# Main_sheet.net
KiCad netlist of a schematic drawn in Altium Designer
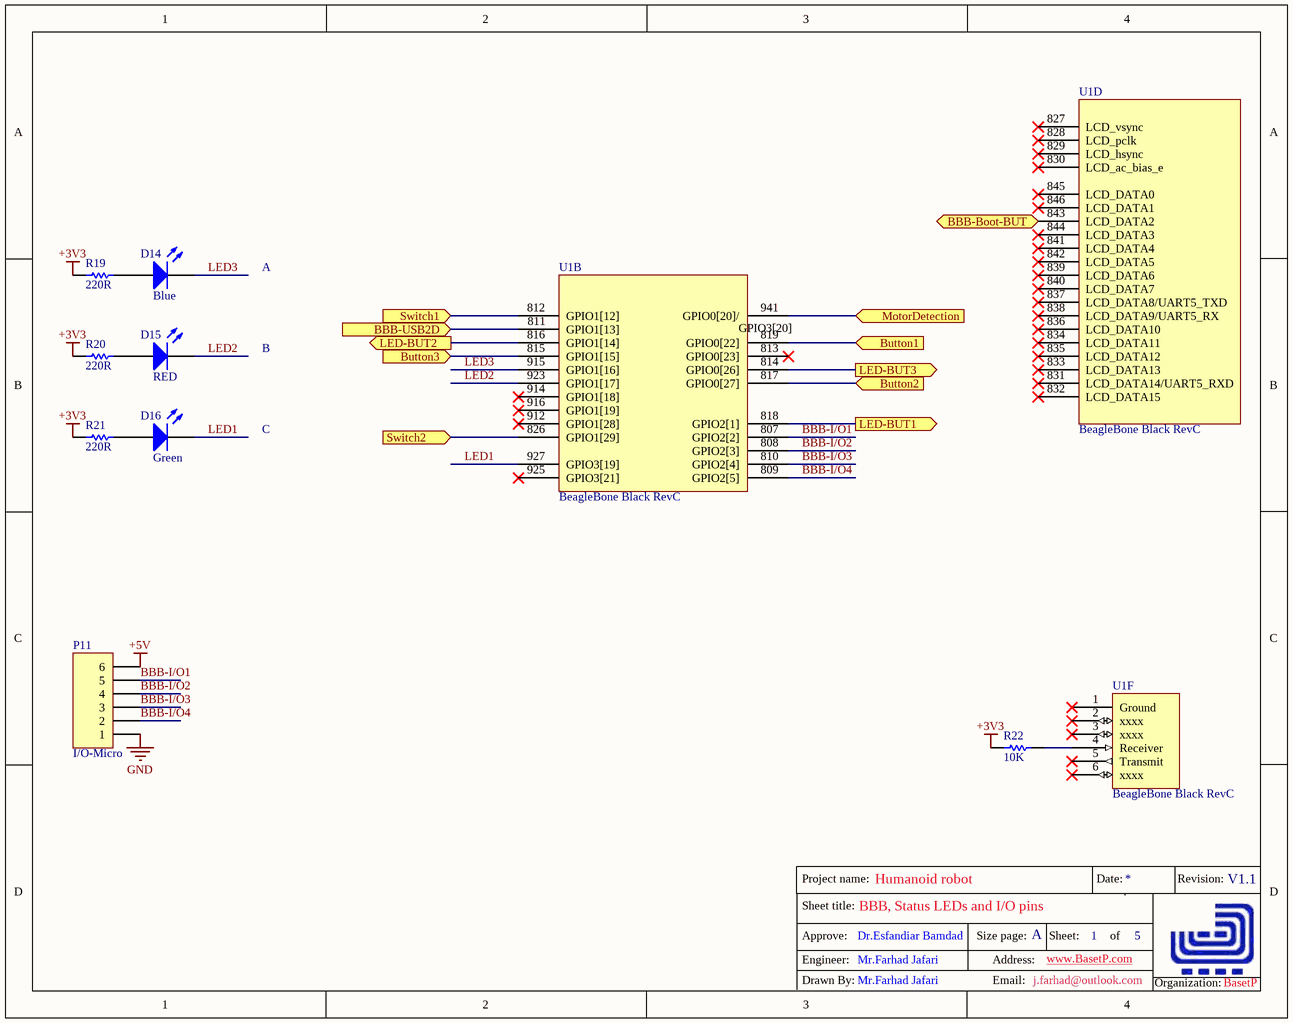
[diagram p0: Main sheet.SchDoc]

(export (version "E")
  (design (tool "Eeschema 10.0.6"))
  (components
    (comp (ref "D14")
      (value "Blue")
      (footprint "led Blue-0805")
      (description "High Performance Chip LED, Amber")
      (fields (field (name "PUBLISHER") "Altium Limited"))
      (libsource (lib "Farhad_Library") (part "LED-BLUE"))
    )
    (comp (ref "D15")
      (value "RED")
      (footprint "LED Red-0805")
      (description "High Performance Chip LED, Amber")
      (fields (field (name "PUBLISHER") "Altium Limited"))
      (libsource (lib "Farhad_Library") (part "LED-RED"))
    )
    (comp (ref "D16")
      (value "Green")
      (footprint "LED Green-0805")
      (description "High Performance Chip LED, Amber")
      (fields (field (name "PUBLISHER") "Altium Limited"))
      (libsource (lib "Farhad_Library") (part "LED-GREEN"))
    )
    (comp (ref "P11")
      (value "I/O-Micro")
      (footprint "HDR1X6")
      (description "Header, 6-Pin")
      (fields (field (name "PUBLISHER") "Altium Limited"))
      (libsource (lib "Farhad_Library") (part "Header 6"))
    )
    (comp (ref "R19")
      (value "220R")
      (footprint "6-0805")
      (fields (field (name "PUBLISHER") "Altium Limited"))
      (libsource (lib "Panasonic Resistor") (part "ERJ6RS"))
    )
    (comp (ref "R20")
      (value "220R")
      (footprint "6-0805")
      (fields (field (name "PUBLISHER") "Altium Limited"))
      (libsource (lib "Panasonic Resistor") (part "ERJ6RS"))
    )
    (comp (ref "R21")
      (value "220R")
      (footprint "6-0805")
      (fields (field (name "PUBLISHER") "Altium Limited"))
      (libsource (lib "Panasonic Resistor") (part "ERJ6RS"))
    )
    (comp (ref "R22")
      (value "10K")
      (footprint "6-0805")
      (fields (field (name "PUBLISHER") "Altium Limited"))
      (libsource (lib "Panasonic Resistor") (part "ERJ6RS"))
    )
    (comp (ref "U1")
      (value "BeagleBone Black RevC")
      (footprint "BBB-C")
      (libsource (lib "Farhad_Library") (part "BeagleBoneBlackRevC"))
    )
  )
  (nets
    (net (code "1") (name "+3V3") (class "Default")
      (node (ref "R19") (pin "1") (pinfunction "1_1") (pintype "passive"))
      (node (ref "R20") (pin "1") (pinfunction "1_1") (pintype "passive"))
      (node (ref "R21") (pin "1") (pinfunction "1_1") (pintype "passive"))
      (node (ref "R22") (pin "1") (pinfunction "1_1") (pintype "passive"))
    )
    (net (code "2") (name "+5V") (class "Default")
      (node (ref "P11") (pin "6") (pinfunction "6_6") (pintype "passive"))
    )
    (net (code "3") (name "/BBB-Boot-BUT") (class "Default")
      (node (ref "U1") (pin "843") (pinfunction "LCD_DATA2_843") (pintype "passive"))
    )
    (net (code "4") (name "/BBB-I{slash}O1") (class "Default")
      (node (ref "P11") (pin "5") (pinfunction "5_5") (pintype "passive"))
      (node (ref "U1") (pin "807") (pinfunction "GPIO2[2]_807") (pintype "passive"))
    )
    (net (code "5") (name "/BBB-I{slash}O2") (class "Default")
      (node (ref "P11") (pin "4") (pinfunction "4_4") (pintype "passive"))
      (node (ref "U1") (pin "808") (pinfunction "GPIO2[3]_808") (pintype "passive"))
    )
    (net (code "6") (name "/BBB-I{slash}O3") (class "Default")
      (node (ref "P11") (pin "3") (pinfunction "3_3") (pintype "passive"))
      (node (ref "U1") (pin "810") (pinfunction "GPIO2[4]_810") (pintype "passive"))
    )
    (net (code "7") (name "/BBB-I{slash}O4") (class "Default")
      (node (ref "P11") (pin "2") (pinfunction "2_2") (pintype "passive"))
      (node (ref "U1") (pin "809") (pinfunction "GPIO2[5]_809") (pintype "passive"))
    )
    (net (code "8") (name "/BBB-USB2D") (class "Default")
      (node (ref "U1") (pin "811") (pinfunction "GPIO1[13]_811") (pintype "passive"))
    )
    (net (code "9") (name "/Button1") (class "Default")
      (node (ref "U1") (pin "819") (pinfunction "GPIO0[22]_819") (pintype "passive"))
    )
    (net (code "10") (name "/Button2") (class "Default")
      (node (ref "U1") (pin "817") (pinfunction "GPIO0[27]_817") (pintype "passive"))
    )
    (net (code "11") (name "/Button3") (class "Default")
      (node (ref "U1") (pin "815") (pinfunction "GPIO1[15]_815") (pintype "passive"))
    )
    (net (code "12") (name "/LED-BUT1") (class "Default")
      (node (ref "U1") (pin "818") (pinfunction "GPIO2[1]_818") (pintype "passive"))
    )
    (net (code "13") (name "/LED-BUT2") (class "Default")
      (node (ref "U1") (pin "816") (pinfunction "GPIO1[14]_816") (pintype "passive"))
    )
    (net (code "14") (name "/LED-BUT3") (class "Default")
      (node (ref "U1") (pin "814") (pinfunction "GPIO0[26]_814") (pintype "passive"))
    )
    (net (code "15") (name "/LED1") (class "Default")
      (node (ref "D16") (pin "2") (pinfunction "K_2") (pintype "passive"))
      (node (ref "U1") (pin "927") (pinfunction "GPIO3[19]_927") (pintype "passive"))
    )
    (net (code "16") (name "/LED2") (class "Default")
      (node (ref "D15") (pin "2") (pinfunction "K_2") (pintype "passive"))
      (node (ref "U1") (pin "923") (pinfunction "GPIO1[17]_923") (pintype "passive"))
    )
    (net (code "17") (name "/LED3") (class "Default")
      (node (ref "D14") (pin "2") (pinfunction "K_2") (pintype "passive"))
      (node (ref "U1") (pin "915") (pinfunction "GPIO1[16]_915") (pintype "passive"))
    )
    (net (code "18") (name "/MotorDetection") (class "Default")
      (node (ref "U1") (pin "941") (pinfunction "GPIO0[20]/_941") (pintype "passive"))
    )
    (net (code "19") (name "/Switch1") (class "Default")
      (node (ref "U1") (pin "812") (pinfunction "GPIO1[12]_812") (pintype "passive"))
    )
    (net (code "20") (name "/Switch2") (class "Default")
      (node (ref "U1") (pin "826") (pinfunction "GPIO1[29]_826") (pintype "passive"))
    )
    (net (code "21") (name "GND") (class "Default")
      (node (ref "P11") (pin "1") (pinfunction "1_1") (pintype "passive"))
    )
    (net (code "22") (name "Net-(D14-A)") (class "Default")
      (node (ref "D14") (pin "1") (pinfunction "A_1") (pintype "passive"))
      (node (ref "R19") (pin "2") (pinfunction "2_2") (pintype "passive"))
    )
    (net (code "23") (name "Net-(D15-A)") (class "Default")
      (node (ref "D15") (pin "1") (pinfunction "A_1") (pintype "passive"))
      (node (ref "R20") (pin "2") (pinfunction "2_2") (pintype "passive"))
    )
    (net (code "24") (name "Net-(D16-A)") (class "Default")
      (node (ref "D16") (pin "1") (pinfunction "A_1") (pintype "passive"))
      (node (ref "R21") (pin "2") (pinfunction "2_2") (pintype "passive"))
    )
    (net (code "25") (name "Net-(U1F-Receiver)") (class "Default")
      (node (ref "R22") (pin "2") (pinfunction "2_2") (pintype "passive"))
      (node (ref "U1") (pin "4") (pinfunction "Receiver_4") (pintype "input"))
    )
    (net (code "26") (name "unconnected-(U1B-GPIO0[23]-Pad813)") (class "Default")
      (node (ref "U1") (pin "813") (pinfunction "GPIO0[23]_813") (pintype "passive+no_connect"))
    )
    (net (code "27") (name "unconnected-(U1B-GPIO1[18]-Pad914)") (class "Default")
      (node (ref "U1") (pin "914") (pinfunction "GPIO1[18]_914") (pintype "passive+no_connect"))
    )
    (net (code "28") (name "unconnected-(U1B-GPIO1[19]-Pad916)") (class "Default")
      (node (ref "U1") (pin "916") (pinfunction "GPIO1[19]_916") (pintype "passive+no_connect"))
    )
    (net (code "29") (name "unconnected-(U1B-GPIO1[28]-Pad912)") (class "Default")
      (node (ref "U1") (pin "912") (pinfunction "GPIO1[28]_912") (pintype "passive+no_connect"))
    )
    (net (code "30") (name "unconnected-(U1B-GPIO3[21]-Pad925)") (class "Default")
      (node (ref "U1") (pin "925") (pinfunction "GPIO3[21]_925") (pintype "passive+no_connect"))
    )
    (net (code "31") (name "unconnected-(U1D-LCD_DATA0-Pad845)") (class "Default")
      (node (ref "U1") (pin "845") (pinfunction "LCD_DATA0_845") (pintype "passive+no_connect"))
    )
    (net (code "32") (name "unconnected-(U1D-LCD_DATA1-Pad846)") (class "Default")
      (node (ref "U1") (pin "846") (pinfunction "LCD_DATA1_846") (pintype "passive+no_connect"))
    )
    (net (code "33") (name "unconnected-(U1D-LCD_DATA3-Pad844)") (class "Default")
      (node (ref "U1") (pin "844") (pinfunction "LCD_DATA3_844") (pintype "passive+no_connect"))
    )
    (net (code "34") (name "unconnected-(U1D-LCD_DATA4-Pad841)") (class "Default")
      (node (ref "U1") (pin "841") (pinfunction "LCD_DATA4_841") (pintype "passive+no_connect"))
    )
    (net (code "35") (name "unconnected-(U1D-LCD_DATA5-Pad842)") (class "Default")
      (node (ref "U1") (pin "842") (pinfunction "LCD_DATA5_842") (pintype "passive+no_connect"))
    )
    (net (code "36") (name "unconnected-(U1D-LCD_DATA6-Pad839)") (class "Default")
      (node (ref "U1") (pin "839") (pinfunction "LCD_DATA6_839") (pintype "passive+no_connect"))
    )
    (net (code "37") (name "unconnected-(U1D-LCD_DATA7-Pad840)") (class "Default")
      (node (ref "U1") (pin "840") (pinfunction "LCD_DATA7_840") (pintype "passive+no_connect"))
    )
    (net (code "38") (name "unconnected-(U1D-LCD_DATA8{slash}UART5_TXD-Pad837)") (class "Default")
      (node (ref "U1") (pin "837") (pinfunction "LCD_DATA8/UART5_TXD_837") (pintype "passive+no_connect"))
    )
    (net (code "39") (name "unconnected-(U1D-LCD_DATA9{slash}UART5_RX-Pad838)") (class "Default")
      (node (ref "U1") (pin "838") (pinfunction "LCD_DATA9/UART5_RX_838") (pintype "passive+no_connect"))
    )
    (net (code "40") (name "unconnected-(U1D-LCD_DATA10-Pad836)") (class "Default")
      (node (ref "U1") (pin "836") (pinfunction "LCD_DATA10_836") (pintype "passive+no_connect"))
    )
    (net (code "41") (name "unconnected-(U1D-LCD_DATA11-Pad834)") (class "Default")
      (node (ref "U1") (pin "834") (pinfunction "LCD_DATA11_834") (pintype "passive+no_connect"))
    )
    (net (code "42") (name "unconnected-(U1D-LCD_DATA12-Pad835)") (class "Default")
      (node (ref "U1") (pin "835") (pinfunction "LCD_DATA12_835") (pintype "passive+no_connect"))
    )
    (net (code "43") (name "unconnected-(U1D-LCD_DATA13-Pad833)") (class "Default")
      (node (ref "U1") (pin "833") (pinfunction "LCD_DATA13_833") (pintype "passive+no_connect"))
    )
    (net (code "44") (name "unconnected-(U1D-LCD_DATA14{slash}UART5_RXD-Pad831)") (class "Default")
      (node (ref "U1") (pin "831") (pinfunction "LCD_DATA14/UART5_RXD_831") (pintype "passive+no_connect"))
    )
    (net (code "45") (name "unconnected-(U1D-LCD_DATA15-Pad832)") (class "Default")
      (node (ref "U1") (pin "832") (pinfunction "LCD_DATA15_832") (pintype "passive+no_connect"))
    )
    (net (code "46") (name "unconnected-(U1D-LCD_ac_bias_e-Pad830)") (class "Default")
      (node (ref "U1") (pin "830") (pinfunction "LCD_ac_bias_e_830") (pintype "passive+no_connect"))
    )
    (net (code "47") (name "unconnected-(U1D-LCD_hsync-Pad829)") (class "Default")
      (node (ref "U1") (pin "829") (pinfunction "LCD_hsync_829") (pintype "passive+no_connect"))
    )
    (net (code "48") (name "unconnected-(U1D-LCD_pclk-Pad828)") (class "Default")
      (node (ref "U1") (pin "828") (pinfunction "LCD_pclk_828") (pintype "passive+no_connect"))
    )
    (net (code "49") (name "unconnected-(U1D-LCD_vsync-Pad827)") (class "Default")
      (node (ref "U1") (pin "827") (pinfunction "LCD_vsync_827") (pintype "passive+no_connect"))
    )
    (net (code "50") (name "unconnected-(U1F-Ground-Pad1)") (class "Default")
      (node (ref "U1") (pin "1") (pinfunction "Ground_1") (pintype "power_in+no_connect"))
    )
    (net (code "51") (name "unconnected-(U1F-Transmit-Pad5)") (class "Default")
      (node (ref "U1") (pin "5") (pinfunction "Transmit_5") (pintype "output+no_connect"))
    )
    (net (code "52") (name "unconnected-(U1F-xxxx-Pad2)") (class "Default")
      (node (ref "U1") (pin "2") (pinfunction "xxxx_2") (pintype "bidirectional+no_connect"))
    )
    (net (code "53") (name "unconnected-(U1F-xxxx-Pad3)") (class "Default")
      (node (ref "U1") (pin "3") (pinfunction "xxxx_3") (pintype "bidirectional+no_connect"))
    )
    (net (code "54") (name "unconnected-(U1F-xxxx-Pad6)") (class "Default")
      (node (ref "U1") (pin "6") (pinfunction "xxxx_6") (pintype "bidirectional+no_connect"))
    )
  )
)
